# OfflineSWD.net
KiCad netlist of a schematic drawn in Altium Designer
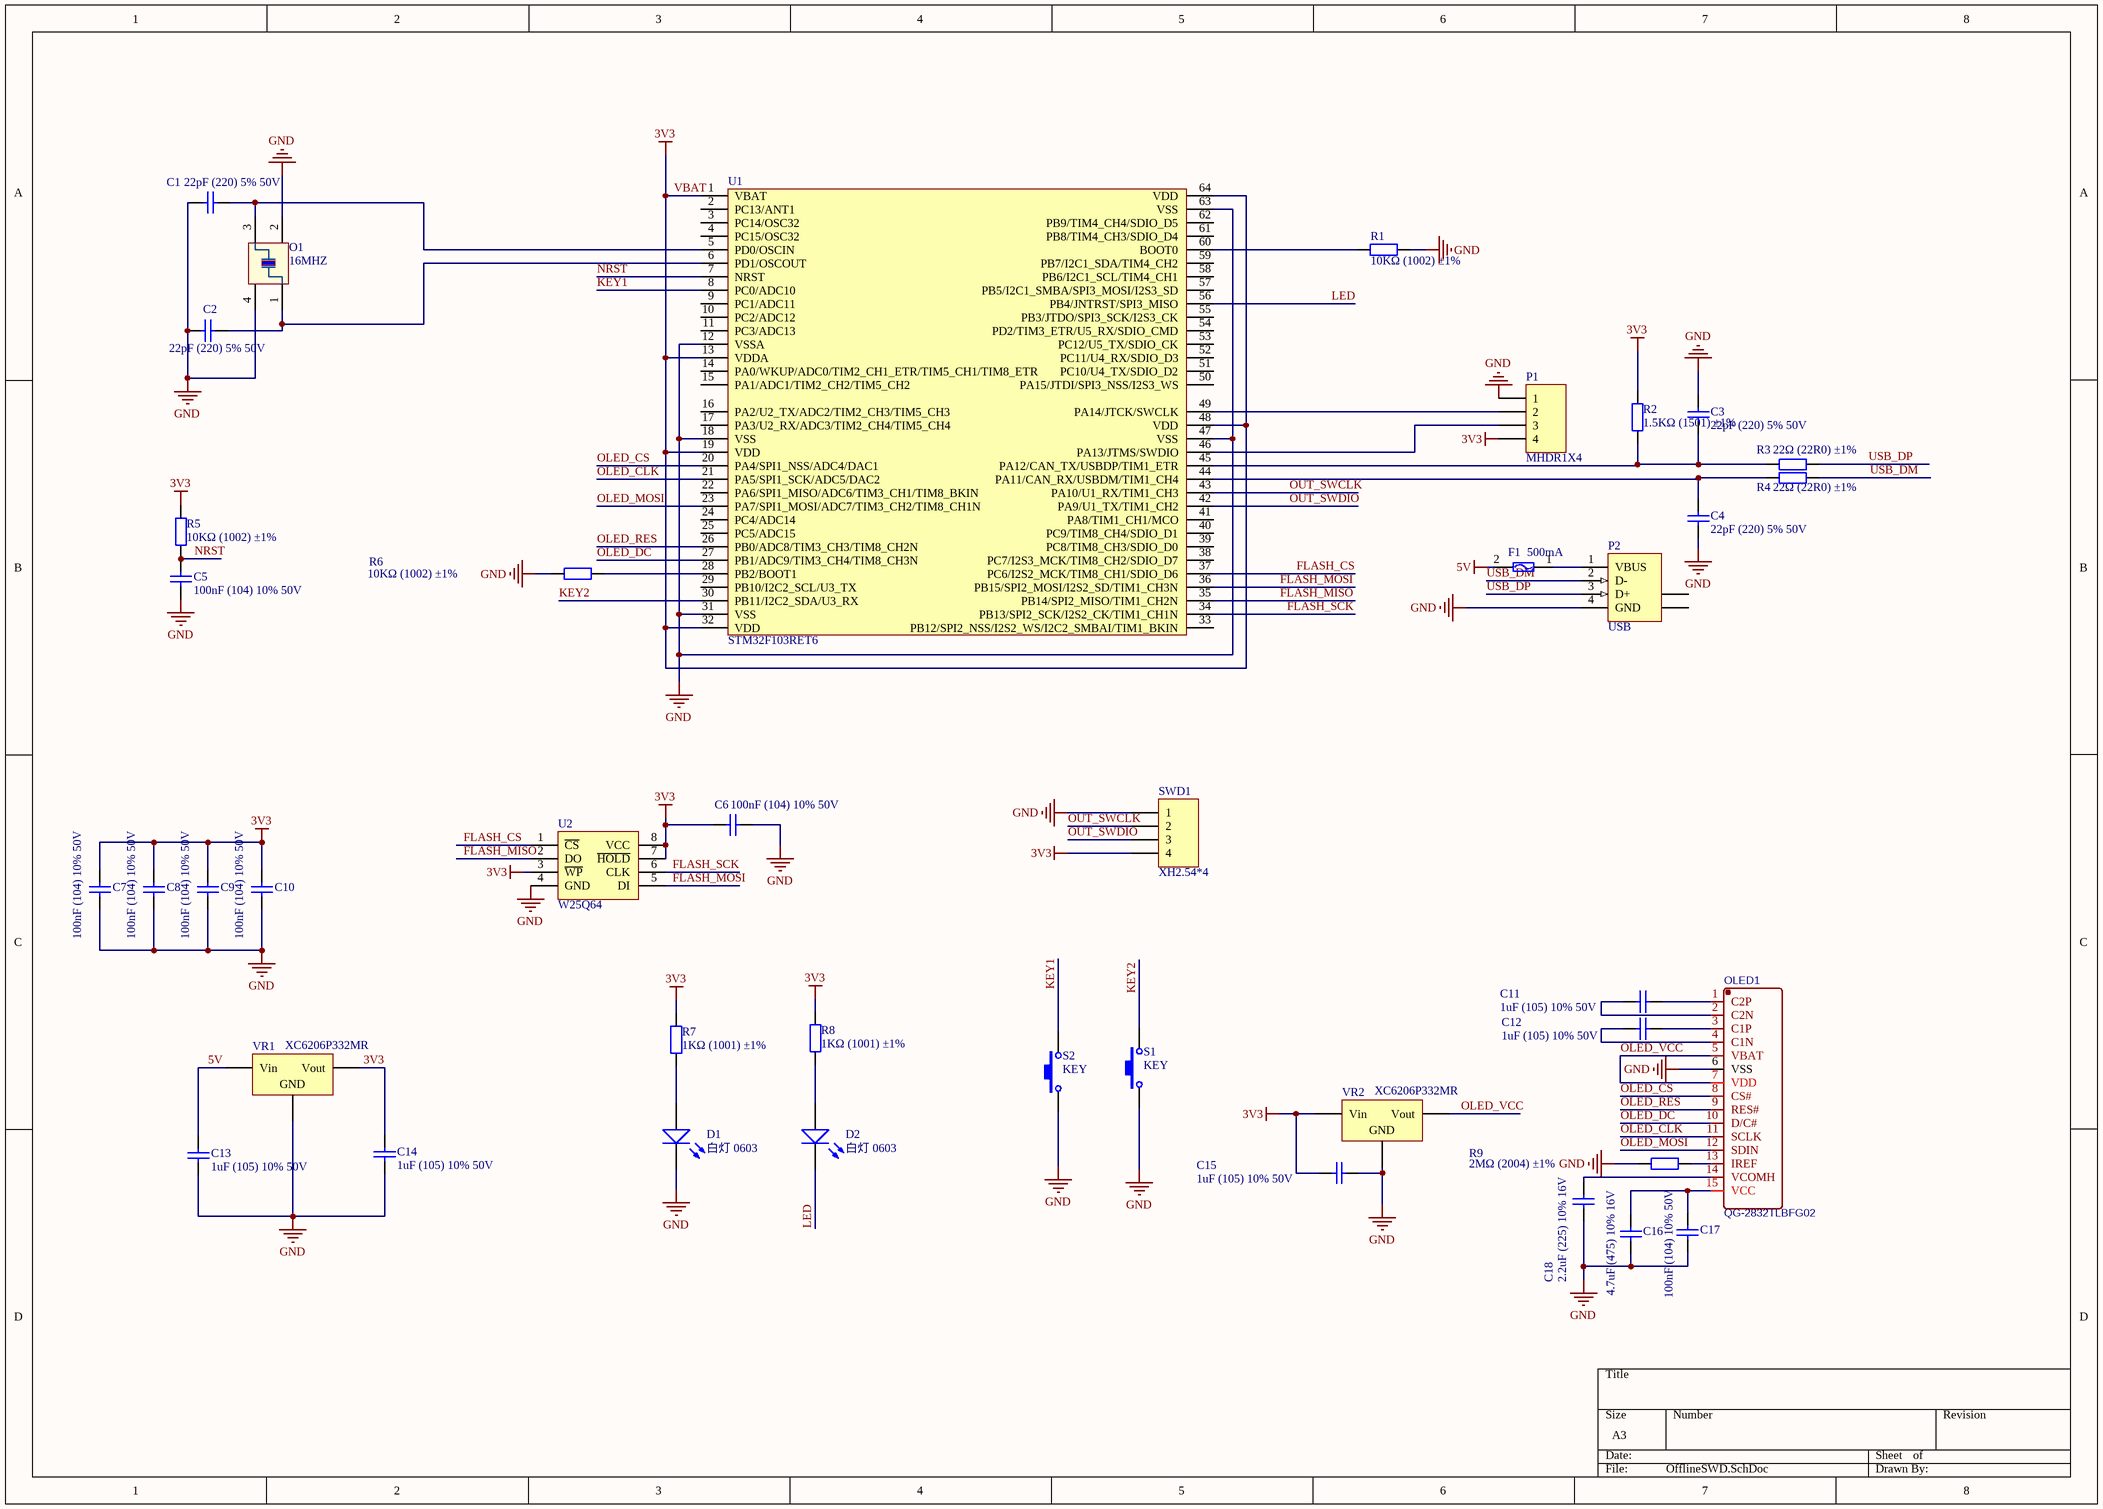
[diagram p0: OfflineSWD.SchDoc]

(export (version "E")
  (design (tool "Eeschema 10.0.6"))
  (components
    (comp (ref "C1")
      (value "22pF (220) 5% 50V")
      (footprint "0603_C")
      (description "贴片电容")
      (libsource (lib "Miscellaneous Devices LC") (part "0603 22pF (220) 5% 50V"))
    )
    (comp (ref "C2")
      (value "22pF (220) 5% 50V")
      (footprint "0603_C")
      (description "贴片电容")
      (libsource (lib "Miscellaneous Devices LC") (part "0603 22pF (220) 5% 50V"))
    )
    (comp (ref "C3")
      (value "22pF (220) 5% 50V")
      (footprint "0603_C")
      (description "贴片电容")
      (libsource (lib "Miscellaneous Devices LC") (part "0603 22pF (220) 5% 50V"))
    )
    (comp (ref "C4")
      (value "22pF (220) 5% 50V")
      (footprint "0603_C")
      (description "贴片电容")
      (libsource (lib "Miscellaneous Devices LC") (part "0603 22pF (220) 5% 50V"))
    )
    (comp (ref "C5")
      (value "100nF (104) 10% 50V")
      (footprint "0603_C")
      (description "贴片电容")
      (libsource (lib "Miscellaneous Devices LC") (part "0603 100nF (104) 10% 50V"))
    )
    (comp (ref "C6")
      (value "100nF (104) 10% 50V")
      (footprint "0603_C")
      (description "贴片电容")
      (libsource (lib "Miscellaneous Devices LC") (part "0603 100nF (104) 10% 50V"))
    )
    (comp (ref "C7")
      (value "100nF (104) 10% 50V")
      (footprint "0603_C")
      (description "贴片电容")
      (libsource (lib "Miscellaneous Devices LC") (part "0603 100nF (104) 10% 50V"))
    )
    (comp (ref "C8")
      (value "100nF (104) 10% 50V")
      (footprint "0603_C")
      (description "贴片电容")
      (libsource (lib "Miscellaneous Devices LC") (part "0603 100nF (104) 10% 50V"))
    )
    (comp (ref "C9")
      (value "100nF (104) 10% 50V")
      (footprint "0603_C")
      (description "贴片电容")
      (libsource (lib "Miscellaneous Devices LC") (part "0603 100nF (104) 10% 50V"))
    )
    (comp (ref "C10")
      (value "100nF (104) 10% 50V")
      (footprint "0603_C")
      (description "贴片电容")
      (libsource (lib "Miscellaneous Devices LC") (part "0603 100nF (104) 10% 50V"))
    )
    (comp (ref "C11")
      (value "1uF (105) 10% 50V")
      (footprint "0603_C")
      (description "贴片电容")
      (libsource (lib "Miscellaneous Devices LC") (part "0603 1uF (105) 10% 50V"))
    )
    (comp (ref "C12")
      (value "1uF (105) 10% 50V")
      (footprint "0603_C")
      (description "贴片电容")
      (libsource (lib "Miscellaneous Devices LC") (part "0603 1uF (105) 10% 50V"))
    )
    (comp (ref "C13")
      (value "1uF (105) 10% 50V")
      (footprint "0603_C")
      (description "贴片电容")
      (libsource (lib "Miscellaneous Devices LC") (part "0603 1uF (105) 10% 50V"))
    )
    (comp (ref "C14")
      (value "1uF (105) 10% 50V")
      (footprint "0603_C")
      (description "贴片电容")
      (libsource (lib "Miscellaneous Devices LC") (part "0603 1uF (105) 10% 50V"))
    )
    (comp (ref "C15")
      (value "1uF (105) 10% 50V")
      (footprint "0603_C")
      (description "贴片电容")
      (libsource (lib "Miscellaneous Devices LC") (part "0603 1uF (105) 10% 50V"))
    )
    (comp (ref "C16")
      (value "4.7uF (475) 10% 16V")
      (footprint "0603_C")
      (description "贴片电容")
      (libsource (lib "Miscellaneous Devices LC") (part "0603 4.7uF (475) 10% 16V"))
    )
    (comp (ref "C17")
      (value "100nF (104) 10% 50V")
      (footprint "0603_C")
      (description "贴片电容")
      (libsource (lib "Miscellaneous Devices LC") (part "0603 100nF (104) 10% 50V"))
    )
    (comp (ref "C18")
      (value "2.2uF (225) 10% 16V")
      (footprint "0603_C")
      (description "贴片电容")
      (libsource (lib "Miscellaneous Devices LC") (part "0603 2.2uF (225) 10% 16V"))
    )
    (comp (ref "D1")
      (value "白灯 0603")
      (footprint "0603_LED_S1")
      (description "发光二极管")
      (libsource (lib "Miscellaneous Devices LC") (part "0603 白灯"))
    )
    (comp (ref "D2")
      (value "白灯 0603")
      (footprint "0603_LED_S1")
      (description "发光二极管")
      (libsource (lib "Miscellaneous Devices LC") (part "0603 白灯"))
    )
    (comp (ref "F1")
      (value "500mA")
      (footprint "0805")
      (description "保险丝，熔断丝")
      (libsource (lib "Free Documents") (part "FUSE"))
    )
    (comp (ref "O1")
      (value "16MHZ")
      (footprint "3225")
      (description "OSC")
      (libsource (lib "altium-import") (part "root_1_OSC_"))
    )
    (comp (ref "OLED1")
      (value "QG-2832TLBFG02")
      (footprint "0.91-OLED")
      (fields (field (name "BOM_SUPPLIER PART") "C91220") (field (name "CONTRIBUTOR") "LCSC"))
      (libsource (lib "0.91-oled") (part "0.91-OLED"))
    )
    (comp (ref "P1")
      (value "MHDR1X4")
      (footprint "MHDR1X4")
      (description "Header, 4-Pin")
      (fields (field (name "PUBLISHER") "Altium Limited"))
      (libsource (lib "Miscellaneous Connectors") (part "MHDR1X4"))
    )
    (comp (ref "P2")
      (value "USB")
      (footprint "USB_A/P_B")
      (description "USB 1.1, Right Angle, SMT, A Type, Plug, 4 Position, Natural")
      (fields (field (name "PUBLISHER") "Altium Limited"))
      (libsource (lib "AMP Serial Bus USB") (part "1470695-2"))
    )
    (comp (ref "R1")
      (value "10KΩ (1002) ±1%")
      (footprint "0603_R")
      (description "贴片电阻")
      (libsource (lib "Miscellaneous Devices LC") (part "0603 10KΩ (1002) 1%"))
    )
    (comp (ref "R2")
      (value "1.5KΩ (1501) ±1%")
      (footprint "0603_R")
      (description "贴片电阻")
      (libsource (lib "Miscellaneous Devices LC") (part "0603 1.5KΩ (1501) 1%"))
    )
    (comp (ref "R3")
      (value "22Ω (22R0) ±1%")
      (footprint "0603_R")
      (description "贴片电阻")
      (libsource (lib "Miscellaneous Devices LC") (part "0603 22Ω (22R0) 1%"))
    )
    (comp (ref "R4")
      (value "22Ω (22R0) ±1%")
      (footprint "0603_R")
      (description "贴片电阻")
      (libsource (lib "Miscellaneous Devices LC") (part "0603 22Ω (22R0) 1%"))
    )
    (comp (ref "R5")
      (value "10KΩ (1002) ±1%")
      (footprint "0603_R")
      (description "贴片电阻")
      (libsource (lib "") (part "0603 10KΩ (1002) 1%_2"))
    )
    (comp (ref "R6")
      (value "10KΩ (1002) ±1%")
      (footprint "0603_R")
      (description "贴片电阻")
      (libsource (lib "") (part "0603 10KΩ (1002) 1%_1"))
    )
    (comp (ref "R7")
      (value "1KΩ (1001) ±1%")
      (footprint "0603_R")
      (description "贴片电阻")
      (libsource (lib "Miscellaneous Devices LC") (part "0603 1KΩ (1001) 1%"))
    )
    (comp (ref "R8")
      (value "1KΩ (1001) ±1%")
      (footprint "0603_R")
      (description "贴片电阻")
      (libsource (lib "Miscellaneous Devices LC") (part "0603 1KΩ (1001) 1%"))
    )
    (comp (ref "R9")
      (value "2MΩ (2004) ±1%")
      (footprint "0603_R")
      (description "贴片电阻")
      (libsource (lib "Miscellaneous Devices LC") (part "0603 2MΩ (2004) 1%"))
    )
    (comp (ref "S1") (value "KEY") (footprint "KEY") (libsource (lib "altium-import") (part "root_1_KEY_")))
    (comp (ref "S2") (value "KEY") (footprint "KEY") (libsource (lib "altium-import") (part "root_1_KEY_")))
    (comp (ref "SWD1")
      (value "XH2.54*4")
      (footprint "XH2.54-WI-4P")
      (description "Header, 4-Pin")
      (fields (field (name "PUBLISHER") "Altium Limited"))
      (libsource (lib "Mogoo-GM_B1-PLCPCB-V1.0") (part "Header 4"))
    )
    (comp (ref "U1")
      (value "STM32F103RET6")
      (footprint "LQFP64")
      (description "STM32F103RxT6")
      (libsource (lib "Free Documents") (part "STM32F103RxT6"))
    )
    (comp (ref "U2")
      (value "W25Q64")
      (footprint "SOP8_W")
      (description "W25Q")
      (libsource (lib "Free Documents") (part "W25Q"))
    )
    (comp (ref "VR1")
      (value "XC6206P332MR")
      (footprint "SOT-23-3L")
      (description "低压差线性稳压(LDO)")
      (libsource (lib "Miscellaneous Devices LC") (part "SOT-23 XC6206P332MR"))
    )
    (comp (ref "VR2")
      (value "XC6206P332MR")
      (footprint "SOT-23-3L")
      (description "低压差线性稳压(LDO)")
      (libsource (lib "Miscellaneous Devices LC") (part "SOT-23 XC6206P332MR"))
    )
  )
  (nets
    (net (code "1") (name "/FLASH_CS") (class "Default")
      (node (ref "U1") (pin "37") (pinfunction "PC6/I2S2_MCK/TIM8_CH1/SDIO_D6_37") (pintype "passive"))
      (node (ref "U2") (pin "1") (pinfunction "~{CS}_1") (pintype "passive"))
    )
    (net (code "2") (name "/FLASH_MISO") (class "Default")
      (node (ref "U1") (pin "35") (pinfunction "PB14/SPI2_MISO/TIM1_CH2N_35") (pintype "passive"))
      (node (ref "U2") (pin "2") (pinfunction "DO_2") (pintype "passive"))
    )
    (net (code "3") (name "/FLASH_MOSI") (class "Default")
      (node (ref "U1") (pin "36") (pinfunction "PB15/SPI2_MOSI/I2S2_SD/TIM1_CH3N_36") (pintype "passive"))
      (node (ref "U2") (pin "5") (pinfunction "DI_5") (pintype "passive"))
    )
    (net (code "4") (name "/FLASH_SCK") (class "Default")
      (node (ref "U1") (pin "34") (pinfunction "PB13/SPI2_SCK/I2S2_CK/TIM1_CH1N_34") (pintype "passive"))
      (node (ref "U2") (pin "6") (pinfunction "CLK_6") (pintype "passive"))
    )
    (net (code "5") (name "/KEY1") (class "Default")
      (node (ref "S2") (pin "2") (pinfunction "2_2") (pintype "power_in"))
      (node (ref "U1") (pin "8") (pinfunction "PC0/ADC10_8") (pintype "passive"))
    )
    (net (code "6") (name "/KEY2") (class "Default")
      (node (ref "S1") (pin "2") (pinfunction "2_2") (pintype "power_in"))
      (node (ref "U1") (pin "30") (pinfunction "PB11/I2C2_SDA/U3_RX_30") (pintype "passive"))
    )
    (net (code "7") (name "/LED") (class "Default")
      (node (ref "D2") (pin "K") (pinfunction "K_K") (pintype "passive"))
      (node (ref "U1") (pin "56") (pinfunction "PB4/JNTRST/SPI3_MISO_56") (pintype "passive"))
    )
    (net (code "8") (name "/NRST") (class "Default")
      (node (ref "C5") (pin "2") (pinfunction "2_2") (pintype "passive"))
      (node (ref "R5") (pin "1") (pinfunction "1_1") (pintype "passive"))
      (node (ref "U1") (pin "7") (pinfunction "NRST_7") (pintype "passive"))
    )
    (net (code "9") (name "/OLED_CLK") (class "Default")
      (node (ref "OLED1") (pin "11") (pinfunction "SCLK_11") (pintype "passive"))
      (node (ref "U1") (pin "21") (pinfunction "PA5/SPI1_SCK/ADC5/DAC2_21") (pintype "passive"))
    )
    (net (code "10") (name "/OLED_CS") (class "Default")
      (node (ref "OLED1") (pin "8") (pinfunction "CS#_8") (pintype "passive"))
      (node (ref "U1") (pin "20") (pinfunction "PA4/SPI1_NSS/ADC4/DAC1_20") (pintype "passive"))
    )
    (net (code "11") (name "/OLED_DC") (class "Default")
      (node (ref "OLED1") (pin "10") (pinfunction "D/C#_10") (pintype "passive"))
      (node (ref "U1") (pin "27") (pinfunction "PB1/ADC9/TIM3_CH4/TIM8_CH3N_27") (pintype "passive"))
    )
    (net (code "12") (name "/OLED_MOSI") (class "Default")
      (node (ref "OLED1") (pin "12") (pinfunction "SDIN_12") (pintype "passive"))
      (node (ref "U1") (pin "23") (pinfunction "PA7/SPI1_MOSI/ADC7/TIM3_CH2/TIM8_CH1N_23") (pintype "passive"))
    )
    (net (code "13") (name "/OLED_RES") (class "Default")
      (node (ref "OLED1") (pin "9") (pinfunction "RES#_9") (pintype "passive"))
      (node (ref "U1") (pin "26") (pinfunction "PB0/ADC8/TIM3_CH3/TIM8_CH2N_26") (pintype "passive"))
    )
    (net (code "14") (name "/OLED_VCC") (class "Default")
      (node (ref "OLED1") (pin "5") (pinfunction "VBAT_5") (pintype "passive"))
      (node (ref "OLED1") (pin "7") (pinfunction "VDD_7") (pintype "passive"))
      (node (ref "VR2") (pin "2") (pinfunction "Vout_2") (pintype "passive"))
    )
    (net (code "15") (name "/OUT_SWCLK") (class "Default")
      (node (ref "SWD1") (pin "2") (pinfunction "2_2") (pintype "passive"))
      (node (ref "U1") (pin "43") (pinfunction "PA10/U1_RX/TIM1_CH3_43") (pintype "passive"))
    )
    (net (code "16") (name "/OUT_SWDIO") (class "Default")
      (node (ref "SWD1") (pin "3") (pinfunction "3_3") (pintype "passive"))
      (node (ref "U1") (pin "42") (pinfunction "PA9/U1_TX/TIM1_CH2_42") (pintype "passive"))
    )
    (net (code "17") (name "/USB_DM") (class "Default")
      (node (ref "P2") (pin "2") (pinfunction "D-_2") (pintype "input"))
      (node (ref "R4") (pin "2") (pinfunction "2_2") (pintype "passive"))
    )
    (net (code "18") (name "/USB_DP") (class "Default")
      (node (ref "P2") (pin "3") (pinfunction "D+_3") (pintype "input"))
      (node (ref "R3") (pin "2") (pinfunction "2_2") (pintype "passive"))
    )
    (net (code "19") (name "3V3") (class "Default")
      (node (ref "C10") (pin "2") (pinfunction "2_2") (pintype "passive"))
      (node (ref "C14") (pin "2") (pinfunction "2_2") (pintype "passive"))
      (node (ref "C15") (pin "1") (pinfunction "1_1") (pintype "passive"))
      (node (ref "C6") (pin "1") (pinfunction "1_1") (pintype "passive"))
      (node (ref "C7") (pin "2") (pinfunction "2_2") (pintype "passive"))
      (node (ref "C8") (pin "2") (pinfunction "2_2") (pintype "passive"))
      (node (ref "C9") (pin "2") (pinfunction "2_2") (pintype "passive"))
      (node (ref "P1") (pin "4") (pinfunction "4_4") (pintype "passive"))
      (node (ref "R2") (pin "1") (pinfunction "1_1") (pintype "passive"))
      (node (ref "R5") (pin "2") (pinfunction "2_2") (pintype "passive"))
      (node (ref "R7") (pin "2") (pinfunction "2_2") (pintype "passive"))
      (node (ref "R8") (pin "2") (pinfunction "2_2") (pintype "passive"))
      (node (ref "SWD1") (pin "4") (pinfunction "4_4") (pintype "passive"))
      (node (ref "U1") (pin "1") (pinfunction "VBAT_1") (pintype "passive"))
      (node (ref "U1") (pin "13") (pinfunction "VDDA_13") (pintype "passive"))
      (node (ref "U1") (pin "19") (pinfunction "VDD_19") (pintype "passive"))
      (node (ref "U1") (pin "32") (pinfunction "VDD_32") (pintype "passive"))
      (node (ref "U1") (pin "48") (pinfunction "VDD_48") (pintype "passive"))
      (node (ref "U1") (pin "64") (pinfunction "VDD_64") (pintype "passive"))
      (node (ref "U2") (pin "3") (pinfunction "~{WP}_3") (pintype "passive"))
      (node (ref "U2") (pin "7") (pinfunction "~{HOLD}_7") (pintype "passive"))
      (node (ref "U2") (pin "8") (pinfunction "VCC_8") (pintype "passive"))
      (node (ref "VR1") (pin "2") (pinfunction "Vout_2") (pintype "passive"))
      (node (ref "VR2") (pin "3") (pinfunction "Vin_3") (pintype "passive"))
    )
    (net (code "20") (name "5V") (class "Default")
      (node (ref "C13") (pin "2") (pinfunction "2_2") (pintype "passive"))
      (node (ref "F1") (pin "2") (pinfunction "5_2") (pintype "passive"))
      (node (ref "VR1") (pin "3") (pinfunction "Vin_3") (pintype "passive"))
    )
    (net (code "21") (name "GND") (class "Default")
      (node (ref "C1") (pin "2") (pinfunction "2_2") (pintype "passive"))
      (node (ref "C10") (pin "1") (pinfunction "1_1") (pintype "passive"))
      (node (ref "C13") (pin "1") (pinfunction "1_1") (pintype "passive"))
      (node (ref "C14") (pin "1") (pinfunction "1_1") (pintype "passive"))
      (node (ref "C15") (pin "2") (pinfunction "2_2") (pintype "passive"))
      (node (ref "C16") (pin "1") (pinfunction "1_1") (pintype "passive"))
      (node (ref "C17") (pin "1") (pinfunction "1_1") (pintype "passive"))
      (node (ref "C18") (pin "1") (pinfunction "1_1") (pintype "passive"))
      (node (ref "C2") (pin "2") (pinfunction "2_2") (pintype "passive"))
      (node (ref "C3") (pin "2") (pinfunction "2_2") (pintype "passive"))
      (node (ref "C4") (pin "1") (pinfunction "1_1") (pintype "passive"))
      (node (ref "C5") (pin "1") (pinfunction "1_1") (pintype "passive"))
      (node (ref "C6") (pin "2") (pinfunction "2_2") (pintype "passive"))
      (node (ref "C7") (pin "1") (pinfunction "1_1") (pintype "passive"))
      (node (ref "C8") (pin "1") (pinfunction "1_1") (pintype "passive"))
      (node (ref "C9") (pin "1") (pinfunction "1_1") (pintype "passive"))
      (node (ref "D1") (pin "K") (pinfunction "K_K") (pintype "passive"))
      (node (ref "O1") (pin "2") (pintype "passive"))
      (node (ref "O1") (pin "4") (pintype "passive"))
      (node (ref "OLED1") (pin "6") (pinfunction "VSS_6") (pintype "passive"))
      (node (ref "P1") (pin "1") (pinfunction "1_1") (pintype "passive"))
      (node (ref "P2") (pin "4") (pinfunction "GND_4") (pintype "power_in"))
      (node (ref "R1") (pin "1") (pinfunction "1_1") (pintype "passive"))
      (node (ref "R6") (pin "1") (pinfunction "1_1") (pintype "passive"))
      (node (ref "R9") (pin "1") (pinfunction "1_1") (pintype "passive"))
      (node (ref "S1") (pin "1") (pinfunction "1_1") (pintype "power_in"))
      (node (ref "S2") (pin "1") (pinfunction "1_1") (pintype "power_in"))
      (node (ref "SWD1") (pin "1") (pinfunction "1_1") (pintype "passive"))
      (node (ref "U1") (pin "12") (pinfunction "VSSA_12") (pintype "passive"))
      (node (ref "U1") (pin "18") (pinfunction "VSS_18") (pintype "passive"))
      (node (ref "U1") (pin "31") (pinfunction "VSS_31") (pintype "passive"))
      (node (ref "U1") (pin "47") (pinfunction "VSS_47") (pintype "passive"))
      (node (ref "U1") (pin "63") (pinfunction "VSS_63") (pintype "passive"))
      (node (ref "U2") (pin "4") (pinfunction "GND_4") (pintype "passive"))
      (node (ref "VR1") (pin "1") (pinfunction "GND_1") (pintype "passive"))
      (node (ref "VR2") (pin "1") (pinfunction "GND_1") (pintype "passive"))
    )
    (net (code "22") (name "Net-(D1-PadA)") (class "Default")
      (node (ref "D1") (pin "A") (pinfunction "A_A") (pintype "passive"))
      (node (ref "R7") (pin "1") (pinfunction "1_1") (pintype "passive"))
    )
    (net (code "23") (name "Net-(D2-PadA)") (class "Default")
      (node (ref "D2") (pin "A") (pinfunction "A_A") (pintype "passive"))
      (node (ref "R8") (pin "1") (pinfunction "1_1") (pintype "passive"))
    )
    (net (code "24") (name "Net-(F1-4)") (class "Default")
      (node (ref "F1") (pin "1") (pinfunction "4_1") (pintype "passive"))
      (node (ref "P2") (pin "1") (pinfunction "VBUS_1") (pintype "power_in"))
    )
    (net (code "25") (name "Net-(OLED1-C1N)") (class "Default")
      (node (ref "C12") (pin "1") (pinfunction "1_1") (pintype "passive"))
      (node (ref "OLED1") (pin "4") (pinfunction "C1N_4") (pintype "passive"))
    )
    (net (code "26") (name "Net-(OLED1-C1P)") (class "Default")
      (node (ref "C12") (pin "2") (pinfunction "2_2") (pintype "passive"))
      (node (ref "OLED1") (pin "3") (pinfunction "C1P_3") (pintype "passive"))
    )
    (net (code "27") (name "Net-(OLED1-C2N)") (class "Default")
      (node (ref "C11") (pin "1") (pinfunction "1_1") (pintype "passive"))
      (node (ref "OLED1") (pin "2") (pinfunction "C2N_2") (pintype "passive"))
    )
    (net (code "28") (name "Net-(OLED1-C2P)") (class "Default")
      (node (ref "C11") (pin "2") (pinfunction "2_2") (pintype "passive"))
      (node (ref "OLED1") (pin "1") (pinfunction "C2P_1") (pintype "passive"))
    )
    (net (code "29") (name "Net-(OLED1-IREF)") (class "Default")
      (node (ref "OLED1") (pin "13") (pinfunction "IREF_13") (pintype "passive"))
      (node (ref "R9") (pin "2") (pinfunction "2_2") (pintype "passive"))
    )
    (net (code "30") (name "Net-(OLED1-VCC)") (class "Default")
      (node (ref "C16") (pin "2") (pinfunction "2_2") (pintype "passive"))
      (node (ref "C17") (pin "2") (pinfunction "2_2") (pintype "passive"))
      (node (ref "OLED1") (pin "15") (pinfunction "VCC_15") (pintype "passive"))
    )
    (net (code "31") (name "Net-(OLED1-VCOMH)") (class "Default")
      (node (ref "C18") (pin "2") (pinfunction "2_2") (pintype "passive"))
      (node (ref "OLED1") (pin "14") (pinfunction "VCOMH_14") (pintype "passive"))
    )
    (net (code "32") (name "Net-(U1-BOOT0)") (class "Default")
      (node (ref "R1") (pin "2") (pinfunction "2_2") (pintype "passive"))
      (node (ref "U1") (pin "60") (pinfunction "BOOT0_60") (pintype "passive"))
    )
    (net (code "33") (name "Net-(U1-PA11{slash}CAN_RX{slash}USBDM{slash}TIM1_CH4)") (class "Default")
      (node (ref "C4") (pin "2") (pinfunction "2_2") (pintype "passive"))
      (node (ref "R4") (pin "1") (pinfunction "1_1") (pintype "passive"))
      (node (ref "U1") (pin "44") (pinfunction "PA11/CAN_RX/USBDM/TIM1_CH4_44") (pintype "passive"))
    )
    (net (code "34") (name "Net-(U1-PA12{slash}CAN_TX{slash}USBDP{slash}TIM1_ETR)") (class "Default")
      (node (ref "C3") (pin "1") (pinfunction "1_1") (pintype "passive"))
      (node (ref "R2") (pin "2") (pinfunction "2_2") (pintype "passive"))
      (node (ref "R3") (pin "1") (pinfunction "1_1") (pintype "passive"))
      (node (ref "U1") (pin "45") (pinfunction "PA12/CAN_TX/USBDP/TIM1_ETR_45") (pintype "passive"))
    )
    (net (code "35") (name "Net-(U1-PA13{slash}JTMS{slash}SWDIO)") (class "Default")
      (node (ref "P1") (pin "3") (pinfunction "3_3") (pintype "passive"))
      (node (ref "U1") (pin "46") (pinfunction "PA13/JTMS/SWDIO_46") (pintype "passive"))
    )
    (net (code "36") (name "Net-(U1-PA14{slash}JTCK{slash}SWCLK)") (class "Default")
      (node (ref "P1") (pin "2") (pinfunction "2_2") (pintype "passive"))
      (node (ref "U1") (pin "49") (pinfunction "PA14/JTCK/SWCLK_49") (pintype "passive"))
    )
    (net (code "37") (name "Net-(U1-PB2{slash}BOOT1)") (class "Default")
      (node (ref "R6") (pin "2") (pinfunction "2_2") (pintype "passive"))
      (node (ref "U1") (pin "28") (pinfunction "PB2/BOOT1_28") (pintype "passive"))
    )
    (net (code "38") (name "Net-(U1-PD0{slash}OSCIN)") (class "Default")
      (node (ref "C1") (pin "1") (pinfunction "1_1") (pintype "passive"))
      (node (ref "O1") (pin "3") (pintype "passive"))
      (node (ref "U1") (pin "5") (pinfunction "PD0/OSCIN_5") (pintype "passive"))
    )
    (net (code "39") (name "Net-(U1-PD1{slash}OSCOUT)") (class "Default")
      (node (ref "C2") (pin "1") (pinfunction "1_1") (pintype "passive"))
      (node (ref "O1") (pin "1") (pintype "passive"))
      (node (ref "U1") (pin "6") (pinfunction "PD1/OSCOUT_6") (pintype "passive"))
    )
    (net (code "40") (name "unconnected-(P2-SHLD-Pad5)") (class "Default")
      (node (ref "P2") (pin "5") (pinfunction "SHLD_5") (pintype "passive"))
    )
    (net (code "41") (name "unconnected-(P2-SHLD-Pad6)") (class "Default")
      (node (ref "P2") (pin "6") (pinfunction "SHLD_6") (pintype "passive"))
    )
    (net (code "42") (name "unconnected-(U1-PA0{slash}WKUP{slash}ADC0{slash}TIM2_CH1_ETR{slash}TIM5_CH1{slash}TIM8_ETR-Pad14)") (class "Default")
      (node (ref "U1") (pin "14") (pinfunction "PA0/WKUP/ADC0/TIM2_CH1_ETR/TIM5_CH1/TIM8_ETR_14") (pintype "passive"))
    )
    (net (code "43") (name "unconnected-(U1-PA1{slash}ADC1{slash}TIM2_CH2{slash}TIM5_CH2-Pad15)") (class "Default")
      (node (ref "U1") (pin "15") (pinfunction "PA1/ADC1/TIM2_CH2/TIM5_CH2_15") (pintype "passive"))
    )
    (net (code "44") (name "unconnected-(U1-PA2{slash}U2_TX{slash}ADC2{slash}TIM2_CH3{slash}TIM5_CH3-Pad16)") (class "Default")
      (node (ref "U1") (pin "16") (pinfunction "PA2/U2_TX/ADC2/TIM2_CH3/TIM5_CH3_16") (pintype "passive"))
    )
    (net (code "45") (name "unconnected-(U1-PA3{slash}U2_RX{slash}ADC3{slash}TIM2_CH4{slash}TIM5_CH4-Pad17)") (class "Default")
      (node (ref "U1") (pin "17") (pinfunction "PA3/U2_RX/ADC3/TIM2_CH4/TIM5_CH4_17") (pintype "passive"))
    )
    (net (code "46") (name "unconnected-(U1-PA6{slash}SPI1_MISO{slash}ADC6{slash}TIM3_CH1{slash}TIM8_BKIN-Pad22)") (class "Default")
      (node (ref "U1") (pin "22") (pinfunction "PA6/SPI1_MISO/ADC6/TIM3_CH1/TIM8_BKIN_22") (pintype "passive"))
    )
    (net (code "47") (name "unconnected-(U1-PA8{slash}TIM1_CH1{slash}MCO-Pad41)") (class "Default")
      (node (ref "U1") (pin "41") (pinfunction "PA8/TIM1_CH1/MCO_41") (pintype "passive"))
    )
    (net (code "48") (name "unconnected-(U1-PA15{slash}JTDI{slash}SPI3_NSS{slash}I2S3_WS-Pad50)") (class "Default")
      (node (ref "U1") (pin "50") (pinfunction "PA15/JTDI/SPI3_NSS/I2S3_WS_50") (pintype "passive"))
    )
    (net (code "49") (name "unconnected-(U1-PB3{slash}JTDO{slash}SPI3_SCK{slash}I2S3_CK-Pad55)") (class "Default")
      (node (ref "U1") (pin "55") (pinfunction "PB3/JTDO/SPI3_SCK/I2S3_CK_55") (pintype "passive"))
    )
    (net (code "50") (name "unconnected-(U1-PB5{slash}I2C1_SMBA{slash}SPI3_MOSI{slash}I2S3_SD-Pad57)") (class "Default")
      (node (ref "U1") (pin "57") (pinfunction "PB5/I2C1_SMBA/SPI3_MOSI/I2S3_SD_57") (pintype "passive"))
    )
    (net (code "51") (name "unconnected-(U1-PB6{slash}I2C1_SCL{slash}TIM4_CH1-Pad58)") (class "Default")
      (node (ref "U1") (pin "58") (pinfunction "PB6/I2C1_SCL/TIM4_CH1_58") (pintype "passive"))
    )
    (net (code "52") (name "unconnected-(U1-PB7{slash}I2C1_SDA{slash}TIM4_CH2-Pad59)") (class "Default")
      (node (ref "U1") (pin "59") (pinfunction "PB7/I2C1_SDA/TIM4_CH2_59") (pintype "passive"))
    )
    (net (code "53") (name "unconnected-(U1-PB8{slash}TIM4_CH3{slash}SDIO_D4-Pad61)") (class "Default")
      (node (ref "U1") (pin "61") (pinfunction "PB8/TIM4_CH3/SDIO_D4_61") (pintype "passive"))
    )
    (net (code "54") (name "unconnected-(U1-PB9{slash}TIM4_CH4{slash}SDIO_D5-Pad62)") (class "Default")
      (node (ref "U1") (pin "62") (pinfunction "PB9/TIM4_CH4/SDIO_D5_62") (pintype "passive"))
    )
    (net (code "55") (name "unconnected-(U1-PB10{slash}I2C2_SCL{slash}U3_TX-Pad29)") (class "Default")
      (node (ref "U1") (pin "29") (pinfunction "PB10/I2C2_SCL/U3_TX_29") (pintype "passive"))
    )
    (net (code "56") (name "unconnected-(U1-PB12{slash}SPI2_NSS{slash}I2S2_WS{slash}I2C2_SMBAI{slash}TIM1_BKIN-Pad33)") (class "Default")
      (node (ref "U1") (pin "33") (pinfunction "PB12/SPI2_NSS/I2S2_WS/I2C2_SMBAI/TIM1_BKIN_33") (pintype "passive"))
    )
    (net (code "57") (name "unconnected-(U1-PC1{slash}ADC11-Pad9)") (class "Default")
      (node (ref "U1") (pin "9") (pinfunction "PC1/ADC11_9") (pintype "passive"))
    )
    (net (code "58") (name "unconnected-(U1-PC2{slash}ADC12-Pad10)") (class "Default")
      (node (ref "U1") (pin "10") (pinfunction "PC2/ADC12_10") (pintype "passive"))
    )
    (net (code "59") (name "unconnected-(U1-PC3{slash}ADC13-Pad11)") (class "Default")
      (node (ref "U1") (pin "11") (pinfunction "PC3/ADC13_11") (pintype "passive"))
    )
    (net (code "60") (name "unconnected-(U1-PC4{slash}ADC14-Pad24)") (class "Default")
      (node (ref "U1") (pin "24") (pinfunction "PC4/ADC14_24") (pintype "passive"))
    )
    (net (code "61") (name "unconnected-(U1-PC5{slash}ADC15-Pad25)") (class "Default")
      (node (ref "U1") (pin "25") (pinfunction "PC5/ADC15_25") (pintype "passive"))
    )
    (net (code "62") (name "unconnected-(U1-PC7{slash}I2S3_MCK{slash}TIM8_CH2{slash}SDIO_D7-Pad38)") (class "Default")
      (node (ref "U1") (pin "38") (pinfunction "PC7/I2S3_MCK/TIM8_CH2/SDIO_D7_38") (pintype "passive"))
    )
    (net (code "63") (name "unconnected-(U1-PC8{slash}TIM8_CH3{slash}SDIO_D0-Pad39)") (class "Default")
      (node (ref "U1") (pin "39") (pinfunction "PC8/TIM8_CH3/SDIO_D0_39") (pintype "passive"))
    )
    (net (code "64") (name "unconnected-(U1-PC9{slash}TIM8_CH4{slash}SDIO_D1-Pad40)") (class "Default")
      (node (ref "U1") (pin "40") (pinfunction "PC9/TIM8_CH4/SDIO_D1_40") (pintype "passive"))
    )
    (net (code "65") (name "unconnected-(U1-PC10{slash}U4_TX{slash}SDIO_D2-Pad51)") (class "Default")
      (node (ref "U1") (pin "51") (pinfunction "PC10/U4_TX/SDIO_D2_51") (pintype "passive"))
    )
    (net (code "66") (name "unconnected-(U1-PC11{slash}U4_RX{slash}SDIO_D3-Pad52)") (class "Default")
      (node (ref "U1") (pin "52") (pinfunction "PC11/U4_RX/SDIO_D3_52") (pintype "passive"))
    )
    (net (code "67") (name "unconnected-(U1-PC12{slash}U5_TX{slash}SDIO_CK-Pad53)") (class "Default")
      (node (ref "U1") (pin "53") (pinfunction "PC12/U5_TX/SDIO_CK_53") (pintype "passive"))
    )
    (net (code "68") (name "unconnected-(U1-PC13{slash}ANT1-Pad2)") (class "Default")
      (node (ref "U1") (pin "2") (pinfunction "PC13/ANT1_2") (pintype "passive"))
    )
    (net (code "69") (name "unconnected-(U1-PC14{slash}OSC32-Pad3)") (class "Default")
      (node (ref "U1") (pin "3") (pinfunction "PC14/OSC32_3") (pintype "passive"))
    )
    (net (code "70") (name "unconnected-(U1-PC15{slash}OSC32-Pad4)") (class "Default")
      (node (ref "U1") (pin "4") (pinfunction "PC15/OSC32_4") (pintype "passive"))
    )
    (net (code "71") (name "unconnected-(U1-PD2{slash}TIM3_ETR{slash}U5_RX{slash}SDIO_CMD-Pad54)") (class "Default")
      (node (ref "U1") (pin "54") (pinfunction "PD2/TIM3_ETR/U5_RX/SDIO_CMD_54") (pintype "passive"))
    )
  )
)
